# BB-M-1_0.net
KiCad netlist of a schematic drawn in EAGLE
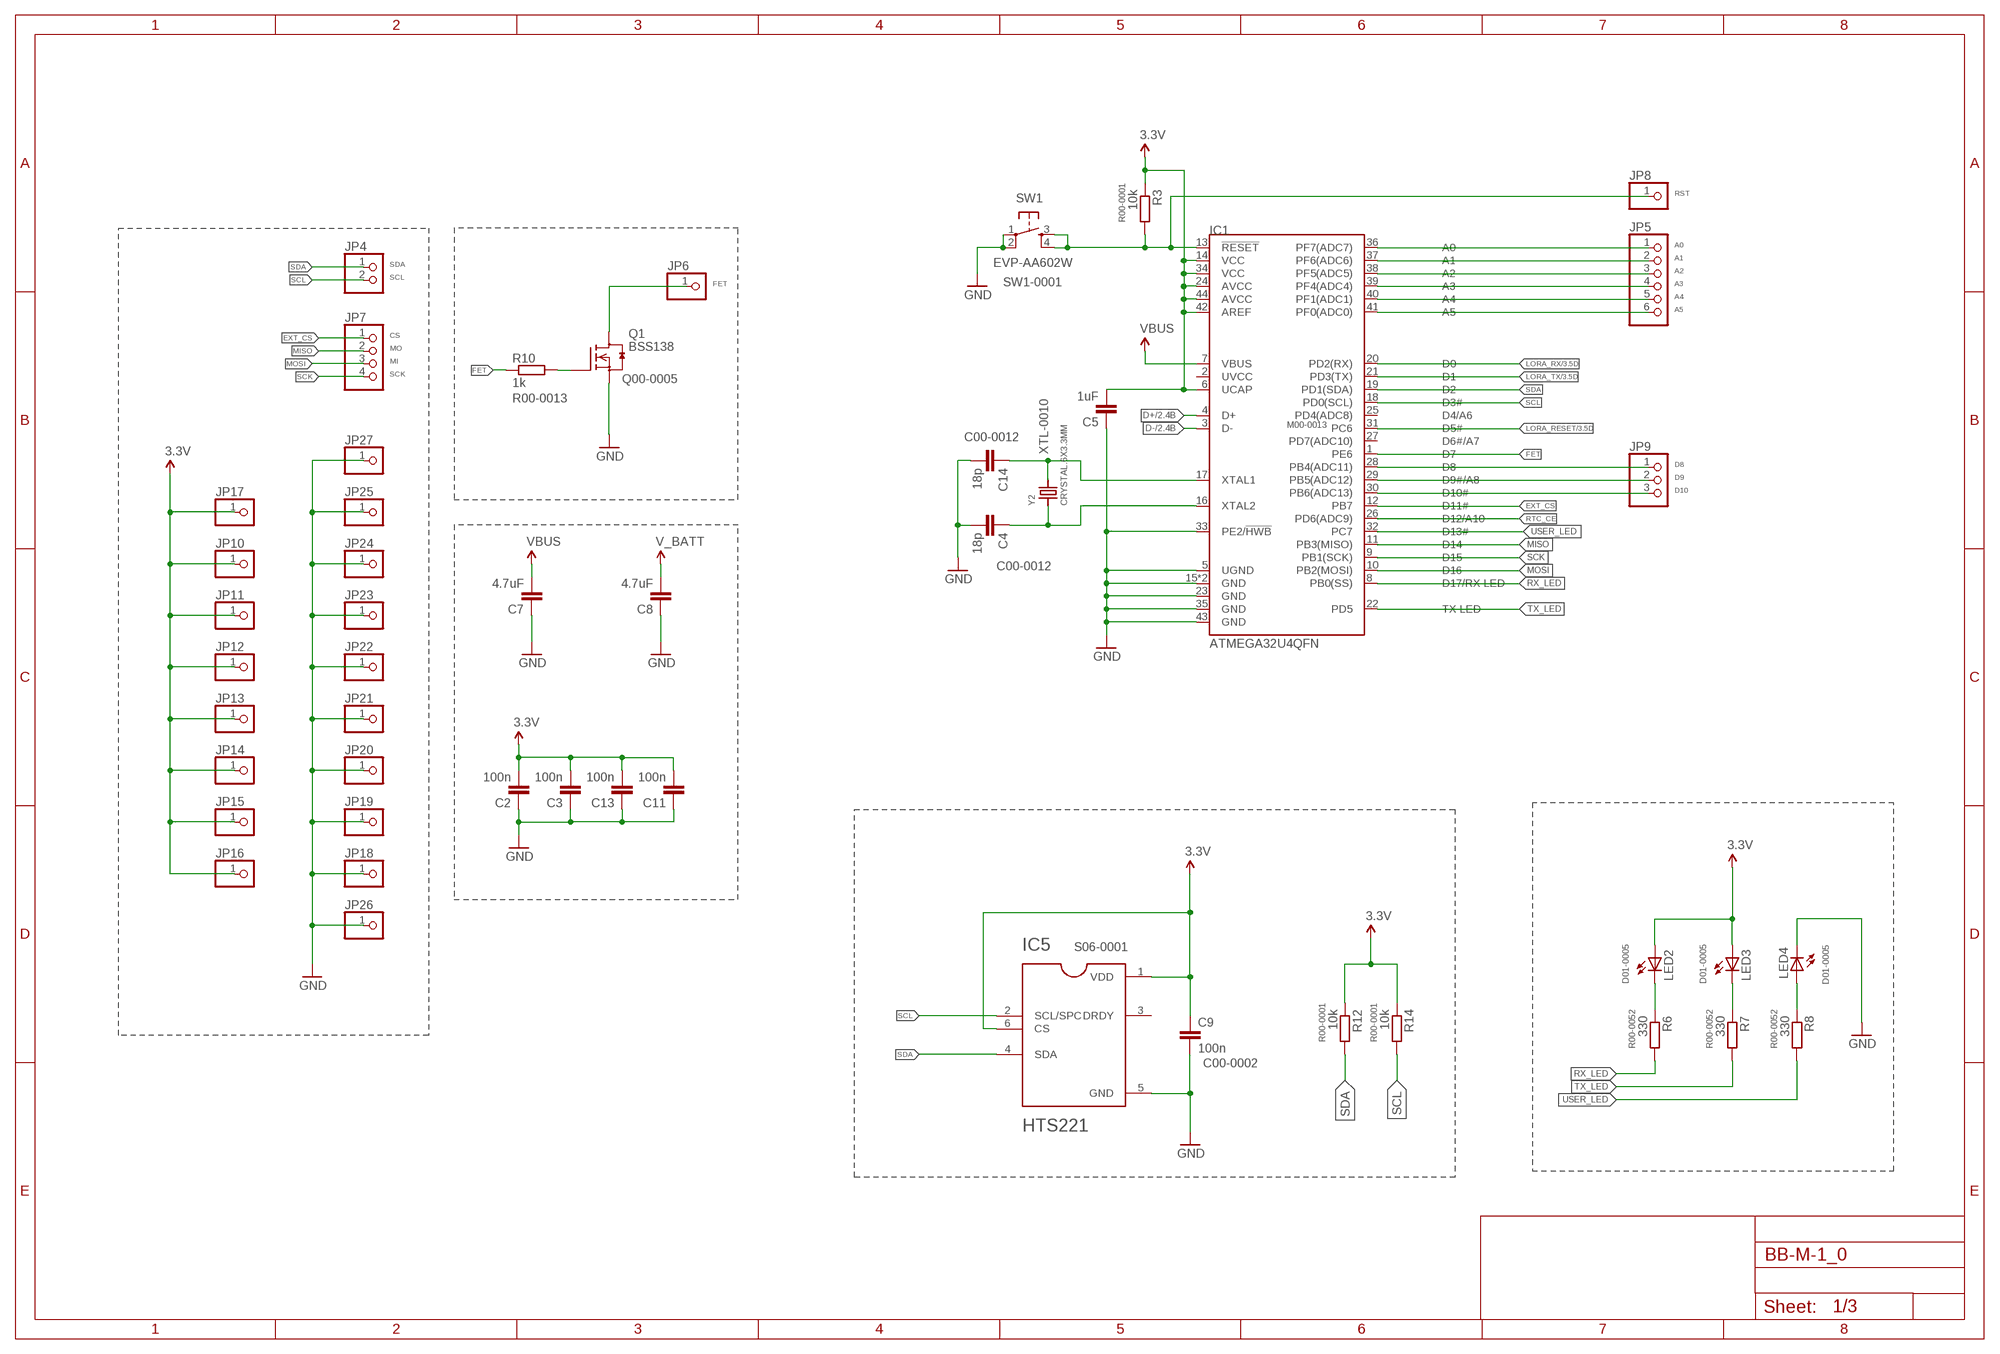
[diagram p0: schematic, sheet 1]
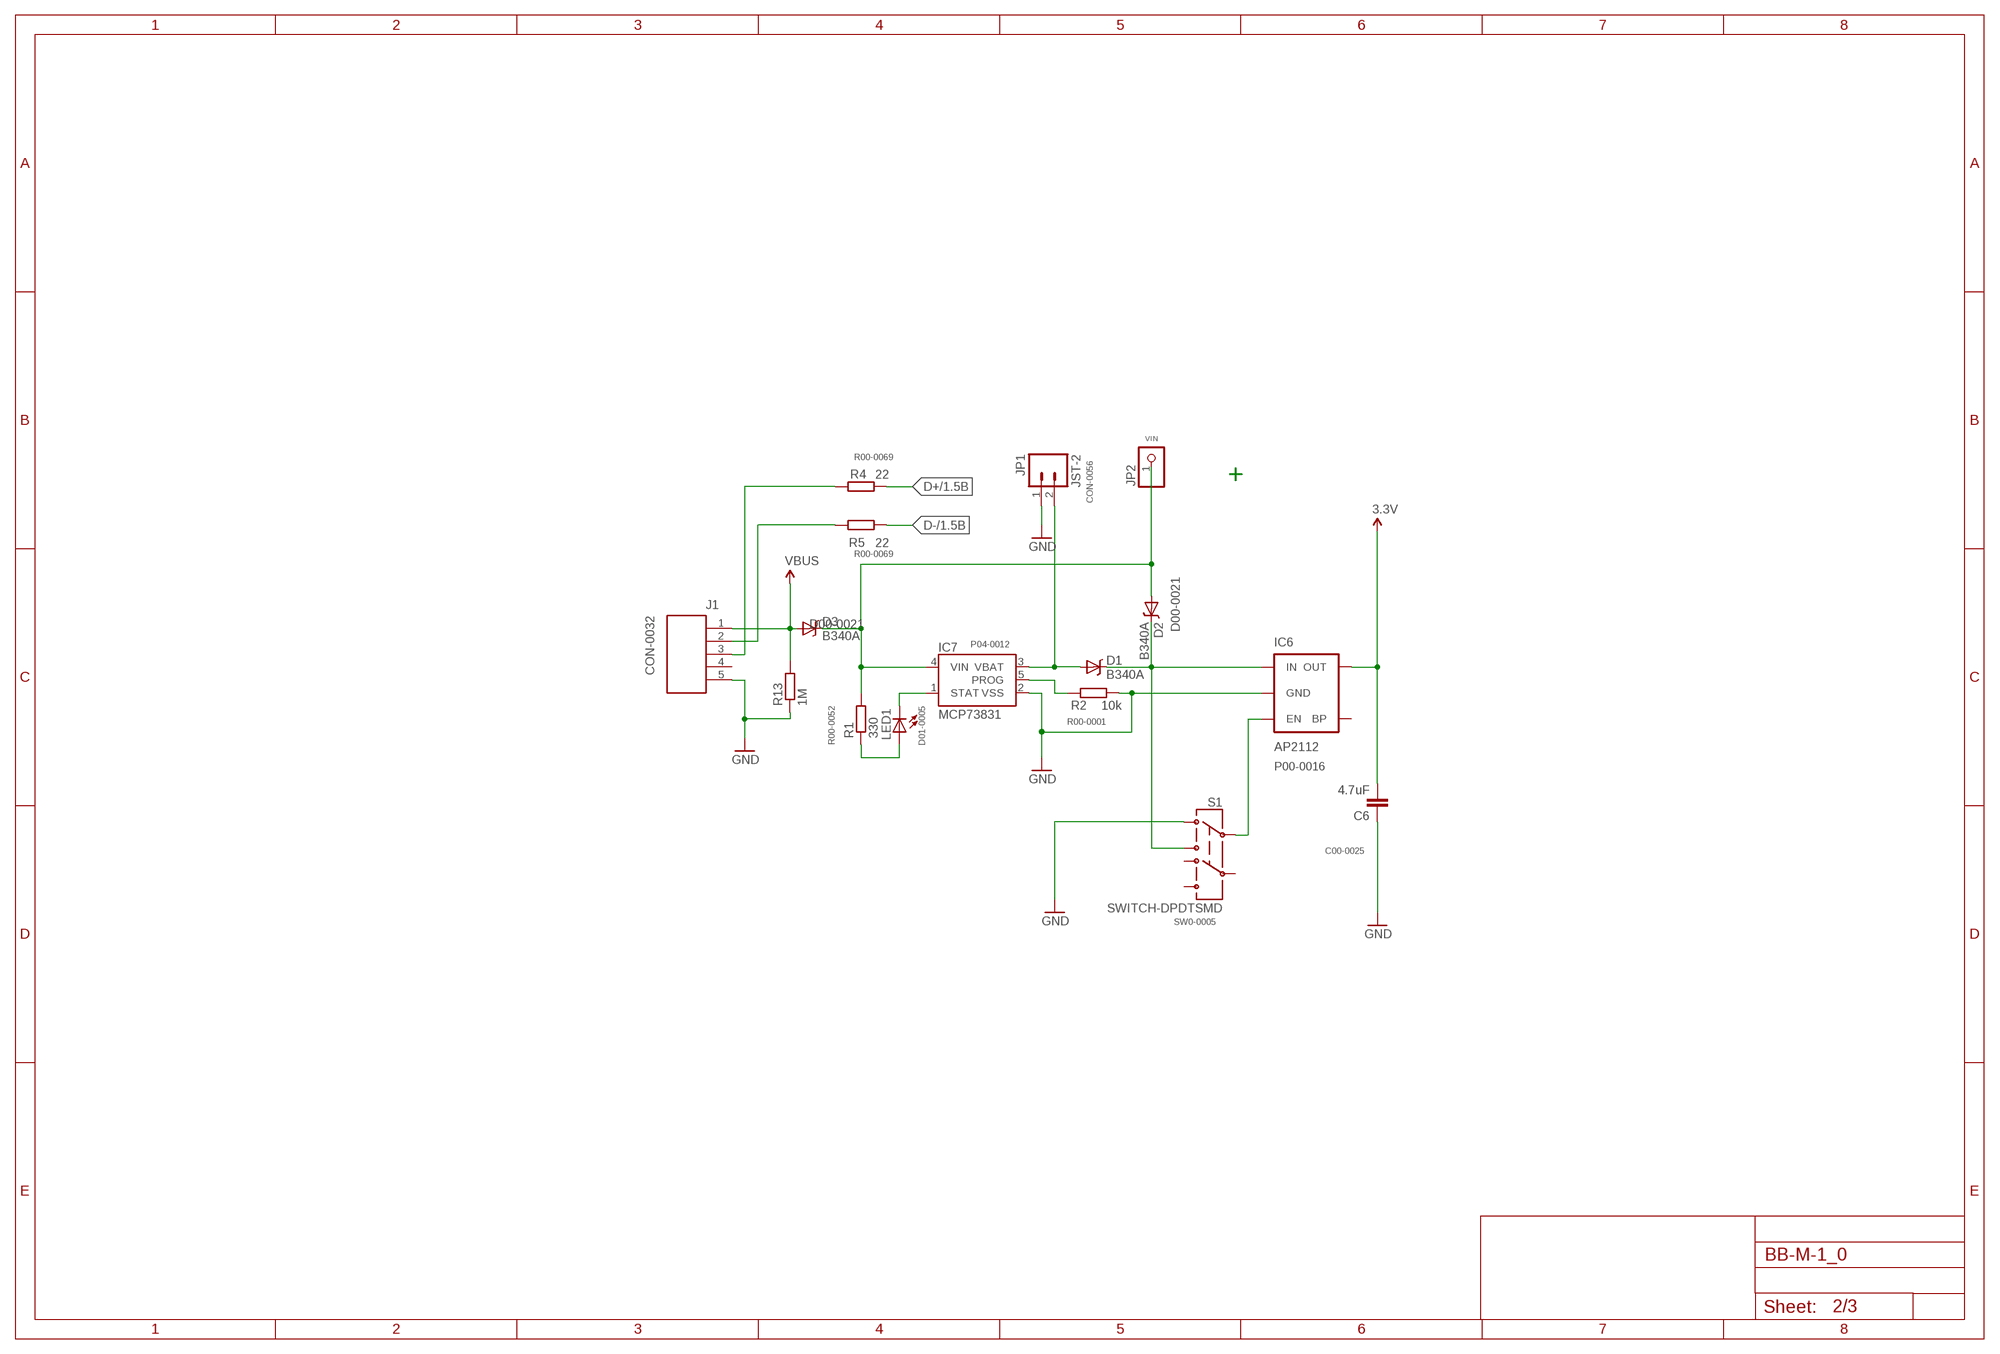
[diagram p1: schematic, sheet 2]
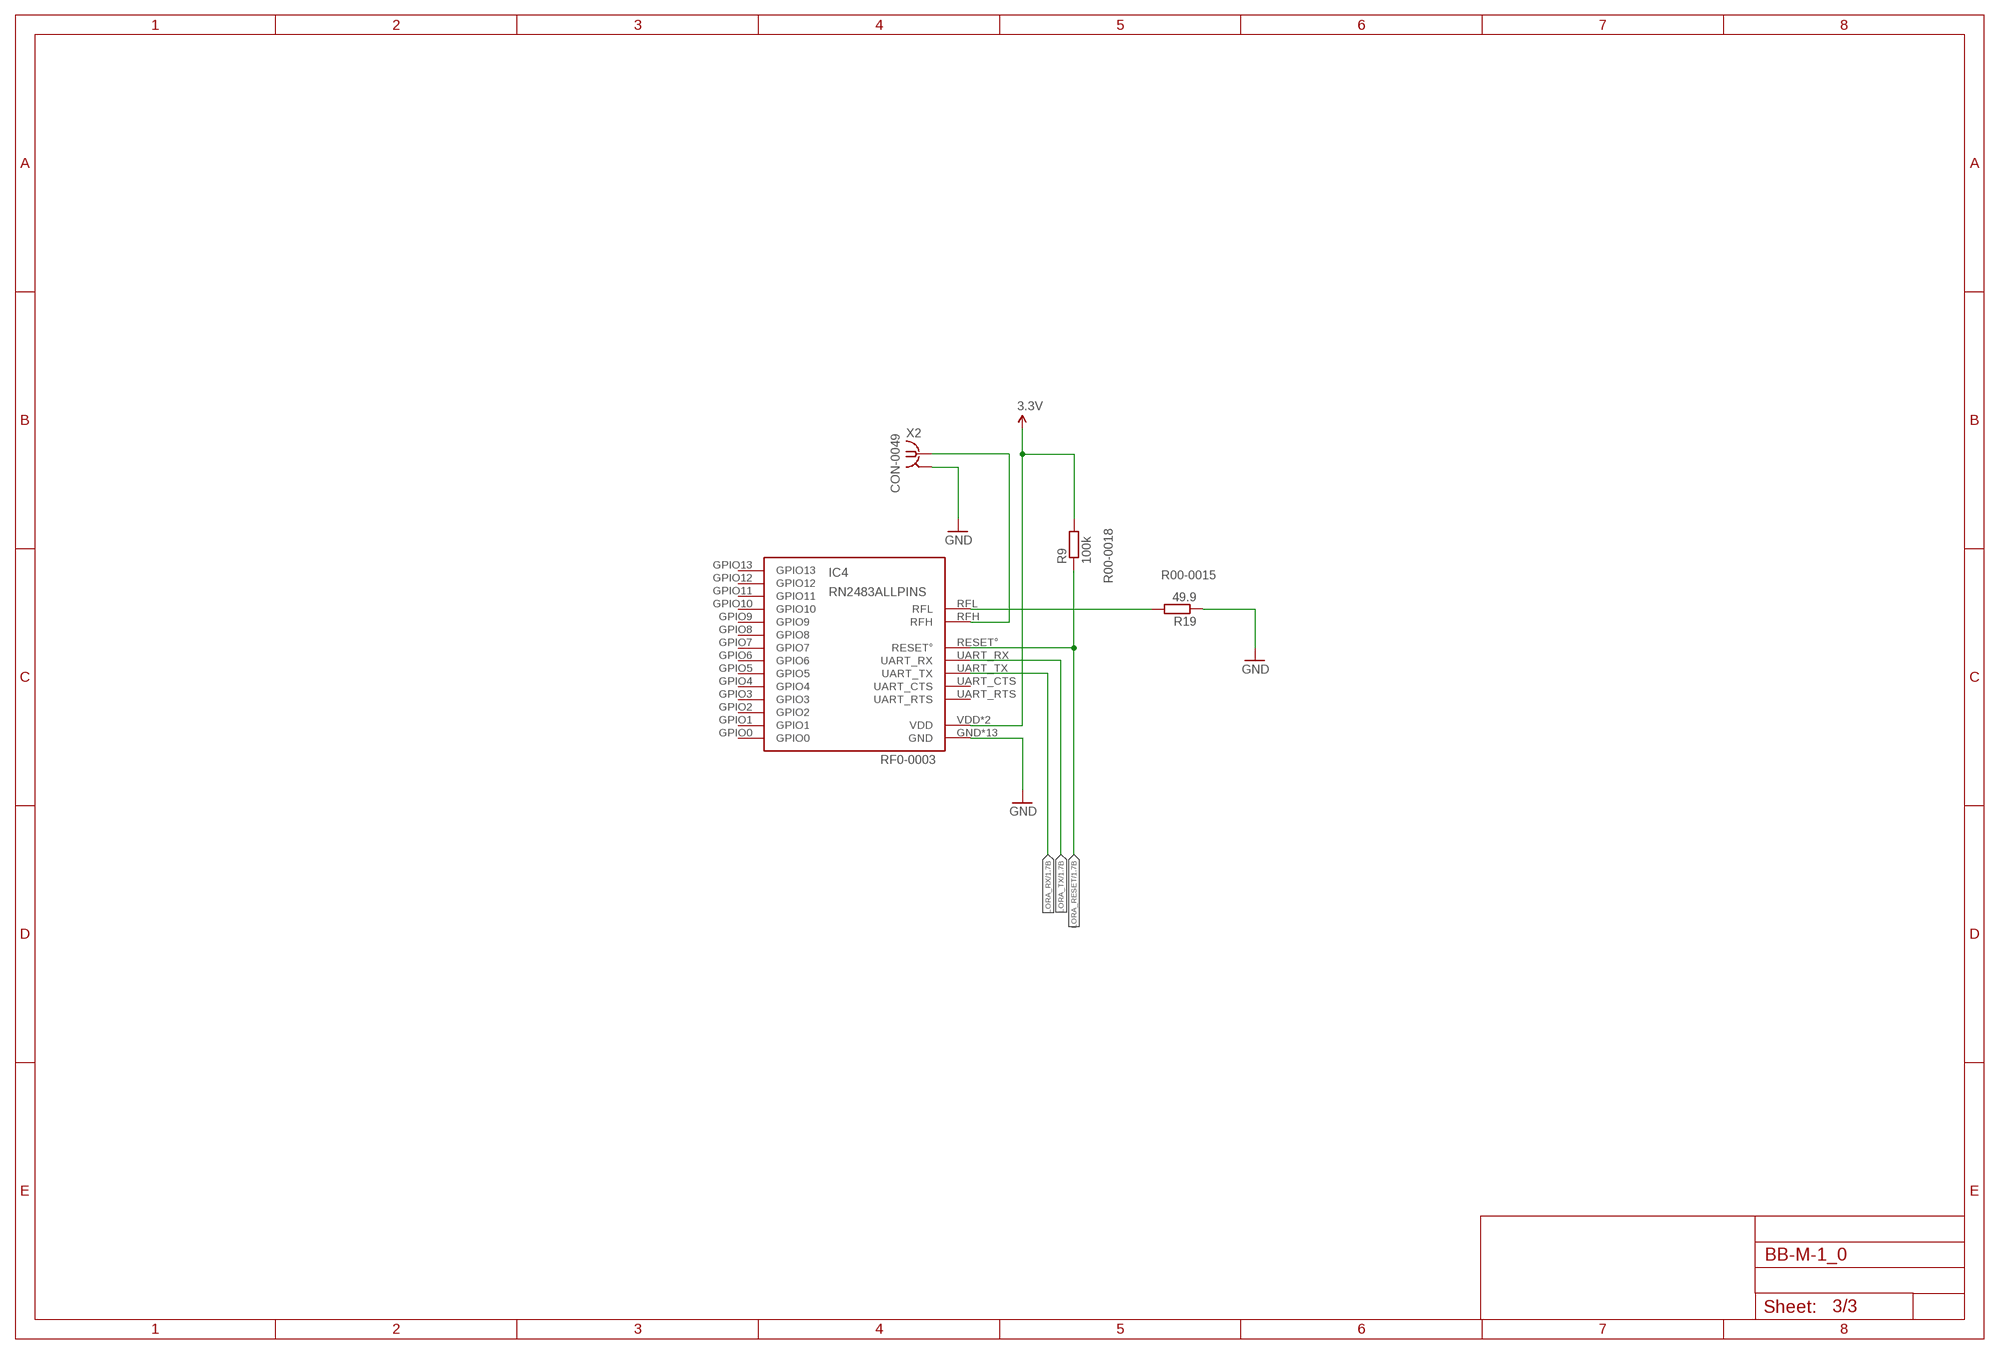
[diagram p2: schematic, sheet 3]

(export (version "E")
  (design (tool "Eeschema 10.0.6"))
  (components
    (comp (ref "IC4")
      (value "RN2483ALLPINS")
      (footprint "eagle-import:RN2483")
      (fields (field (name "NASPN") "RF0-0003"))
      (libsource (lib "eagle-import") (part "RN2483ALLPINS"))
    )
    (comp (ref "R9")
      (value "100k")
      (footprint "eagle-import:R0402")
      (fields (field (name "NASPN") "R00-0018"))
      (libsource (lib "eagle-import") (part "R-EU_R0402"))
    )
    (comp (ref "R19")
      (value "49.9")
      (footprint "eagle-import:R0402")
      (fields (field (name "NASPN") "R00-0015"))
      (libsource (lib "eagle-import") (part "R-EU_R0402"))
    )
    (comp (ref "X2")
      (value "132414")
      (footprint "eagle-import:132414")
      (fields (field (name "NASPN") "CON-0049"))
      (libsource (lib "eagle-import") (part "132414"))
    )
    (comp (ref "C2")
      (value "100n")
      (footprint "eagle-import:C0402")
      (libsource (lib "eagle-import") (part "C-EUC0402"))
    )
    (comp (ref "C3")
      (value "100n")
      (footprint "eagle-import:C0402")
      (libsource (lib "eagle-import") (part "C-EUC0402"))
    )
    (comp (ref "C4")
      (value "18p")
      (footprint "eagle-import:C0402")
      (fields (field (name "NASPN") "C00-0012"))
      (libsource (lib "eagle-import") (part "C-EUC0402"))
    )
    (comp (ref "C5")
      (value "1uF")
      (footprint "eagle-import:C0402")
      (libsource (lib "eagle-import") (part "C-EUC0402"))
    )
    (comp (ref "C7")
      (value "4.7uF")
      (footprint "eagle-import:C0603")
      (libsource (lib "eagle-import") (part "C-EUC0603"))
    )
    (comp (ref "C8")
      (value "4.7uF")
      (footprint "eagle-import:C0603")
      (libsource (lib "eagle-import") (part "C-EUC0603"))
    )
    (comp (ref "C9")
      (value "100n")
      (footprint "eagle-import:C0402")
      (fields (field (name "NASPN") "C00-0002"))
      (libsource (lib "eagle-import") (part "C-EUC0402"))
    )
    (comp (ref "C11")
      (value "100n")
      (footprint "eagle-import:C0402")
      (libsource (lib "eagle-import") (part "C-EUC0402"))
    )
    (comp (ref "C13")
      (value "100n")
      (footprint "eagle-import:C0402")
      (libsource (lib "eagle-import") (part "C-EUC0402"))
    )
    (comp (ref "C14")
      (value "18p")
      (footprint "eagle-import:C0402")
      (fields (field (name "NASPN") "C00-0012"))
      (libsource (lib "eagle-import") (part "C-EUC0402"))
    )
    (comp (ref "IC1")
      (value "ATMEGA32U4QFN")
      (footprint "eagle-import:QFN-44")
      (fields (field (name "NASPN") "M00-0013"))
      (libsource (lib "eagle-import") (part "ATMEGA32U4QFN"))
    )
    (comp (ref "IC5")
      (value "HTS221")
      (footprint "eagle-import:LGA6R75P3X2_200X200X90")
      (fields (field (name "NASPN") "S06-0001"))
      (libsource (lib "eagle-import") (part "HTS221"))
    )
    (comp (ref "JP4")
      (value "HEADER-1X2ROUND")
      (footprint "eagle-import:1X02_ROUND")
      (libsource (lib "eagle-import") (part "HEADER-1X2ROUND"))
    )
    (comp (ref "JP5")
      (value "HEADER-1X6ROUND")
      (footprint "eagle-import:1X06_ROUND")
      (libsource (lib "eagle-import") (part "HEADER-1X6ROUND"))
    )
    (comp (ref "JP6")
      (value "HEADER-1X1ROUND")
      (footprint "eagle-import:1X01_ROUND")
      (libsource (lib "eagle-import") (part "HEADER-1X1ROUND"))
    )
    (comp (ref "JP7")
      (value "HEADER-1X4ROUND")
      (footprint "eagle-import:1X04_ROUND")
      (libsource (lib "eagle-import") (part "HEADER-1X4ROUND"))
    )
    (comp (ref "JP8")
      (value "HEADER-1X1ROUND")
      (footprint "eagle-import:1X01_ROUND")
      (libsource (lib "eagle-import") (part "HEADER-1X1ROUND"))
    )
    (comp (ref "JP9")
      (value "HEADER-1X3ROUND")
      (footprint "eagle-import:1X03_ROUND")
      (libsource (lib "eagle-import") (part "HEADER-1X3ROUND"))
    )
    (comp (ref "JP10")
      (value "HEADER-1X1ROUND")
      (footprint "eagle-import:1X01_ROUND")
      (libsource (lib "eagle-import") (part "HEADER-1X1ROUND"))
    )
    (comp (ref "JP11")
      (value "HEADER-1X1ROUND")
      (footprint "eagle-import:1X01_ROUND")
      (libsource (lib "eagle-import") (part "HEADER-1X1ROUND"))
    )
    (comp (ref "JP12")
      (value "HEADER-1X1ROUND")
      (footprint "eagle-import:1X01_ROUND")
      (libsource (lib "eagle-import") (part "HEADER-1X1ROUND"))
    )
    (comp (ref "JP13")
      (value "HEADER-1X1ROUND")
      (footprint "eagle-import:1X01_ROUND")
      (libsource (lib "eagle-import") (part "HEADER-1X1ROUND"))
    )
    (comp (ref "JP14")
      (value "HEADER-1X1ROUND")
      (footprint "eagle-import:1X01_ROUND")
      (libsource (lib "eagle-import") (part "HEADER-1X1ROUND"))
    )
    (comp (ref "JP15")
      (value "HEADER-1X1ROUND")
      (footprint "eagle-import:1X01_ROUND")
      (libsource (lib "eagle-import") (part "HEADER-1X1ROUND"))
    )
    (comp (ref "JP16")
      (value "HEADER-1X1ROUND")
      (footprint "eagle-import:1X01_ROUND")
      (libsource (lib "eagle-import") (part "HEADER-1X1ROUND"))
    )
    (comp (ref "JP17")
      (value "HEADER-1X1ROUND")
      (footprint "eagle-import:1X01_ROUND")
      (libsource (lib "eagle-import") (part "HEADER-1X1ROUND"))
    )
    (comp (ref "JP18")
      (value "HEADER-1X1ROUND")
      (footprint "eagle-import:1X01_ROUND")
      (libsource (lib "eagle-import") (part "HEADER-1X1ROUND"))
    )
    (comp (ref "JP19")
      (value "HEADER-1X1ROUND")
      (footprint "eagle-import:1X01_ROUND")
      (libsource (lib "eagle-import") (part "HEADER-1X1ROUND"))
    )
    (comp (ref "JP20")
      (value "HEADER-1X1ROUND")
      (footprint "eagle-import:1X01_ROUND")
      (libsource (lib "eagle-import") (part "HEADER-1X1ROUND"))
    )
    (comp (ref "JP21")
      (value "HEADER-1X1ROUND")
      (footprint "eagle-import:1X01_ROUND")
      (libsource (lib "eagle-import") (part "HEADER-1X1ROUND"))
    )
    (comp (ref "JP22")
      (value "HEADER-1X1ROUND")
      (footprint "eagle-import:1X01_ROUND")
      (libsource (lib "eagle-import") (part "HEADER-1X1ROUND"))
    )
    (comp (ref "JP23")
      (value "HEADER-1X1ROUND")
      (footprint "eagle-import:1X01_ROUND")
      (libsource (lib "eagle-import") (part "HEADER-1X1ROUND"))
    )
    (comp (ref "JP24")
      (value "HEADER-1X1ROUND")
      (footprint "eagle-import:1X01_ROUND")
      (libsource (lib "eagle-import") (part "HEADER-1X1ROUND"))
    )
    (comp (ref "JP25")
      (value "HEADER-1X1ROUND")
      (footprint "eagle-import:1X01_ROUND")
      (libsource (lib "eagle-import") (part "HEADER-1X1ROUND"))
    )
    (comp (ref "JP26")
      (value "HEADER-1X1ROUND")
      (footprint "eagle-import:1X01_ROUND")
      (libsource (lib "eagle-import") (part "HEADER-1X1ROUND"))
    )
    (comp (ref "JP27")
      (value "HEADER-1X1ROUND")
      (footprint "eagle-import:1X01_ROUND")
      (libsource (lib "eagle-import") (part "HEADER-1X1ROUND"))
    )
    (comp (ref "LED2")
      (value "LED0603")
      (footprint "eagle-import:LED-0603")
      (fields (field (name "NASPN") "D01-0005"))
      (libsource (lib "eagle-import") (part "LED0603"))
    )
    (comp (ref "LED3")
      (value "LED0603")
      (footprint "eagle-import:LED-0603")
      (fields (field (name "NASPN") "D01-0005"))
      (libsource (lib "eagle-import") (part "LED0603"))
    )
    (comp (ref "LED4")
      (value "LED0603")
      (footprint "eagle-import:LED-0603")
      (fields (field (name "NASPN") "D01-0005"))
      (libsource (lib "eagle-import") (part "LED0603"))
    )
    (comp (ref "Q1")
      (value "BSS138")
      (footprint "eagle-import:SOT23")
      (fields (field (name "NASPN") "Q00-0005"))
      (libsource (lib "eagle-import") (part "BSS138"))
    )
    (comp (ref "R3")
      (value "10k")
      (footprint "eagle-import:R0402")
      (fields (field (name "NASPN") "R00-0001"))
      (libsource (lib "eagle-import") (part "R-EU_R0402"))
    )
    (comp (ref "R6")
      (value "330")
      (footprint "eagle-import:R0402")
      (fields (field (name "NASPN") "R00-0052"))
      (libsource (lib "eagle-import") (part "R-EU_R0402"))
    )
    (comp (ref "R7")
      (value "330")
      (footprint "eagle-import:R0402")
      (fields (field (name "NASPN") "R00-0052"))
      (libsource (lib "eagle-import") (part "R-EU_R0402"))
    )
    (comp (ref "R8")
      (value "330")
      (footprint "eagle-import:R0402")
      (fields (field (name "NASPN") "R00-0052"))
      (libsource (lib "eagle-import") (part "R-EU_R0402"))
    )
    (comp (ref "R10")
      (value "1k")
      (footprint "eagle-import:R0402")
      (fields (field (name "NASPN") "R00-0013"))
      (libsource (lib "eagle-import") (part "R-EU_R0402"))
    )
    (comp (ref "R12")
      (value "10k")
      (footprint "eagle-import:R0402")
      (fields (field (name "NASPN") "R00-0001"))
      (libsource (lib "eagle-import") (part "R-EU_R0402"))
    )
    (comp (ref "R14")
      (value "10k")
      (footprint "eagle-import:R0402")
      (fields (field (name "NASPN") "R00-0001"))
      (libsource (lib "eagle-import") (part "R-EU_R0402"))
    )
    (comp (ref "SW1")
      (value "EVP-AA602W")
      (footprint "eagle-import:UUS_BUTTON")
      (fields (field (name "NASPN") "SW1-0001"))
      (libsource (lib "eagle-import") (part "SPST_TACT"))
    )
    (comp (ref "Y2")
      (value "CRYSTAL.6X3.3MM")
      (footprint "eagle-import:6X3.3MM")
      (fields (field (name "NASPN") "XTL-0010"))
      (libsource (lib "eagle-import") (part "CRYSTAL.6X3.3MM"))
    )
    (comp (ref "C6")
      (value "4.7uF")
      (footprint "eagle-import:C0603")
      (fields (field (name "NASPN") "C00-0025"))
      (libsource (lib "eagle-import") (part "C-EUC0603"))
    )
    (comp (ref "D1")
      (value "B340A")
      (footprint "eagle-import:SMA-DIODE")
      (libsource (lib "eagle-import") (part "DIODE-SCHOTTKY_"))
    )
    (comp (ref "D2")
      (value "B340A")
      (footprint "eagle-import:SMA-DIODE")
      (fields (field (name "NASPN") "D00-0021"))
      (libsource (lib "eagle-import") (part "DIODE-SCHOTTKY_"))
    )
    (comp (ref "D3")
      (value "B340A")
      (footprint "eagle-import:SMA-DIODE")
      (fields (field (name "NASPN") "D00-0021"))
      (libsource (lib "eagle-import") (part "DIODE-SCHOTTKY_"))
    )
    (comp (ref "IC6")
      (value "AP2112")
      (footprint "eagle-import:SOT23-5")
      (fields (field (name "NASPN") "P00-0016"))
      (libsource (lib "eagle-import") (part "V_REG_MIC5219SMD"))
    )
    (comp (ref "IC7")
      (value "MCP73831")
      (footprint "eagle-import:SOT23-5")
      (fields (field (name "NASPN") "P04-0012"))
      (libsource (lib "eagle-import") (part "MCP73831"))
    )
    (comp (ref "J1")
      (value "629105136821")
      (footprint "eagle-import:629105136821")
      (fields (field (name "NASPN") "CON-0032"))
      (libsource (lib "eagle-import") (part "629105136821"))
    )
    (comp (ref "JP1")
      (value "JST-2")
      (footprint "eagle-import:JST-2-SMD")
      (fields (field (name "NASPN") "CON-0056"))
      (libsource (lib "eagle-import") (part "M02-JST-2MM-SMT"))
    )
    (comp (ref "JP2")
      (value "PINHD-1X1CB")
      (footprint "eagle-import:1X01-CLEANBIG")
      (libsource (lib "eagle-import") (part "PINHD-1X1CB"))
    )
    (comp (ref "LED1")
      (value "LED0603")
      (footprint "eagle-import:LED-0603")
      (fields (field (name "NASPN") "D01-0005"))
      (libsource (lib "eagle-import") (part "LED0603"))
    )
    (comp (ref "R1")
      (value "330")
      (footprint "eagle-import:R0402")
      (fields (field (name "NASPN") "R00-0052"))
      (libsource (lib "eagle-import") (part "R-EU_R0402"))
    )
    (comp (ref "R2")
      (value "10k")
      (footprint "eagle-import:R0402")
      (fields (field (name "NASPN") "R00-0001"))
      (libsource (lib "eagle-import") (part "R-EU_R0402"))
    )
    (comp (ref "R4")
      (value "22")
      (footprint "eagle-import:R0402")
      (fields (field (name "NASPN") "R00-0069"))
      (libsource (lib "eagle-import") (part "R-EU_R0402"))
    )
    (comp (ref "R5")
      (value "22")
      (footprint "eagle-import:R0402")
      (fields (field (name "NASPN") "R00-0069"))
      (libsource (lib "eagle-import") (part "R-EU_R0402"))
    )
    (comp (ref "R13")
      (value "1M")
      (footprint "eagle-import:R0402")
      (libsource (lib "eagle-import") (part "R-EU_R0402"))
    )
    (comp (ref "S1")
      (value "SWITCH-DPDTSMD")
      (footprint "eagle-import:AYZ0202")
      (fields (field (name "NASPN") "SW0-0005"))
      (libsource (lib "eagle-import") (part "SWITCH-DPDTSMD"))
    )
  )
  (nets
    (net (code "1") (name "3.3V") (class "Default")
      (node (ref "C11") (pin "2") (pinfunction "2_2") (pintype "passive"))
      (node (ref "C13") (pin "2") (pinfunction "2_2") (pintype "passive"))
      (node (ref "C2") (pin "2") (pinfunction "2_2") (pintype "passive"))
      (node (ref "C3") (pin "2") (pinfunction "2_2") (pintype "passive"))
      (node (ref "C5") (pin "2") (pinfunction "2_2") (pintype "passive"))
      (node (ref "C6") (pin "2") (pinfunction "2_2") (pintype "passive"))
      (node (ref "C9") (pin "1") (pinfunction "1_1") (pintype "passive"))
      (node (ref "IC1") (pin "14") (pinfunction "VCC_14") (pintype "bidirectional"))
      (node (ref "IC1") (pin "24") (pinfunction "AVCC_24") (pintype "bidirectional"))
      (node (ref "IC1") (pin "34") (pinfunction "VCC_34") (pintype "bidirectional"))
      (node (ref "IC1") (pin "42") (pinfunction "AREF_42") (pintype "bidirectional"))
      (node (ref "IC1") (pin "44") (pinfunction "AVCC_44") (pintype "bidirectional"))
      (node (ref "IC1") (pin "6") (pinfunction "UCAP_6") (pintype "bidirectional"))
      (node (ref "IC4") (pin "VDD") (pinfunction "VDD_VDD") (pintype "bidirectional"))
      (node (ref "IC4") (pin "VDD2") (pinfunction "VDD_VDD2") (pintype "bidirectional"))
      (node (ref "IC5") (pin "1") (pinfunction "VDD_1") (pintype "power_in"))
      (node (ref "IC5") (pin "6") (pinfunction "CS_6") (pintype "input"))
      (node (ref "IC6") (pin "5") (pinfunction "OUT_5") (pintype "passive"))
      (node (ref "JP10") (pin "1") (pinfunction "1_1") (pintype "passive"))
      (node (ref "JP11") (pin "1") (pinfunction "1_1") (pintype "passive"))
      (node (ref "JP12") (pin "1") (pinfunction "1_1") (pintype "passive"))
      (node (ref "JP13") (pin "1") (pinfunction "1_1") (pintype "passive"))
      (node (ref "JP14") (pin "1") (pinfunction "1_1") (pintype "passive"))
      (node (ref "JP15") (pin "1") (pinfunction "1_1") (pintype "passive"))
      (node (ref "JP16") (pin "1") (pinfunction "1_1") (pintype "passive"))
      (node (ref "JP17") (pin "1") (pinfunction "1_1") (pintype "passive"))
      (node (ref "LED2") (pin "A") (pinfunction "A_A") (pintype "passive"))
      (node (ref "LED3") (pin "A") (pinfunction "A_A") (pintype "passive"))
      (node (ref "R12") (pin "1") (pinfunction "1_1") (pintype "passive"))
      (node (ref "R14") (pin "1") (pinfunction "1_1") (pintype "passive"))
      (node (ref "R3") (pin "1") (pinfunction "1_1") (pintype "passive"))
      (node (ref "R9") (pin "2") (pinfunction "2_2") (pintype "passive"))
    )
    (net (code "2") (name "5V") (class "Default")
      (node (ref "C7") (pin "2") (pinfunction "2_2") (pintype "passive"))
      (node (ref "D3") (pin "A") (pinfunction "A_A") (pintype "passive"))
      (node (ref "IC1") (pin "7") (pinfunction "VBUS_7") (pintype "bidirectional"))
      (node (ref "J1") (pin "1") (pinfunction "1_1") (pintype "passive"))
      (node (ref "R13") (pin "2") (pinfunction "2_2") (pintype "passive"))
    )
    (net (code "3") (name "D+") (class "Default")
      (node (ref "IC1") (pin "4") (pinfunction "D+_4") (pintype "bidirectional"))
      (node (ref "R4") (pin "1") (pinfunction "1_1") (pintype "passive"))
    )
    (net (code "4") (name "D-") (class "Default")
      (node (ref "IC1") (pin "3") (pinfunction "D-_3") (pintype "bidirectional"))
      (node (ref "R5") (pin "1") (pinfunction "1_1") (pintype "passive"))
    )
    (net (code "5") (name "EXT_CS") (class "Default")
      (node (ref "IC1") (pin "12") (pinfunction "PB7_12") (pintype "bidirectional"))
      (node (ref "JP7") (pin "1") (pinfunction "1_1") (pintype "passive"))
    )
    (net (code "6") (name "FET") (class "Default")
      (node (ref "IC1") (pin "1") (pinfunction "PE6_1") (pintype "bidirectional"))
      (node (ref "R10") (pin "1") (pinfunction "1_1") (pintype "passive"))
    )
    (net (code "7") (name "GND") (class "Default")
      (node (ref "C11") (pin "1") (pinfunction "1_1") (pintype "passive"))
      (node (ref "C13") (pin "1") (pinfunction "1_1") (pintype "passive"))
      (node (ref "C14") (pin "2") (pinfunction "2_2") (pintype "passive"))
      (node (ref "C2") (pin "1") (pinfunction "1_1") (pintype "passive"))
      (node (ref "C3") (pin "1") (pinfunction "1_1") (pintype "passive"))
      (node (ref "C4") (pin "2") (pinfunction "2_2") (pintype "passive"))
      (node (ref "C5") (pin "1") (pinfunction "1_1") (pintype "passive"))
      (node (ref "C6") (pin "1") (pinfunction "1_1") (pintype "passive"))
      (node (ref "C7") (pin "1") (pinfunction "1_1") (pintype "passive"))
      (node (ref "C8") (pin "1") (pinfunction "1_1") (pintype "passive"))
      (node (ref "C9") (pin "2") (pinfunction "2_2") (pintype "passive"))
      (node (ref "IC1") (pin "15") (pinfunction "GND_15") (pintype "bidirectional"))
      (node (ref "IC1") (pin "23") (pinfunction "GND_23") (pintype "bidirectional"))
      (node (ref "IC1") (pin "33") (pinfunction "PE2/~{HWB}_33") (pintype "bidirectional"))
      (node (ref "IC1") (pin "35") (pinfunction "GND_35") (pintype "bidirectional"))
      (node (ref "IC1") (pin "43") (pinfunction "GND_43") (pintype "bidirectional"))
      (node (ref "IC1") (pin "5") (pinfunction "UGND_5") (pintype "bidirectional"))
      (node (ref "IC1") (pin "EPAD") (pinfunction "GND_EPAD") (pintype "bidirectional"))
      (node (ref "IC4") (pin "GND") (pinfunction "GND_GND") (pintype "bidirectional"))
      (node (ref "IC4") (pin "GND1") (pinfunction "GND_GND1") (pintype "bidirectional"))
      (node (ref "IC4") (pin "GND10") (pinfunction "GND_GND10") (pintype "bidirectional"))
      (node (ref "IC4") (pin "GND11") (pinfunction "GND_GND11") (pintype "bidirectional"))
      (node (ref "IC4") (pin "GND12") (pinfunction "GND_GND12") (pintype "bidirectional"))
      (node (ref "IC4") (pin "GND2") (pinfunction "GND_GND2") (pintype "bidirectional"))
      (node (ref "IC4") (pin "GND3") (pinfunction "GND_GND3") (pintype "bidirectional"))
      (node (ref "IC4") (pin "GND4") (pinfunction "GND_GND4") (pintype "bidirectional"))
      (node (ref "IC4") (pin "GND5") (pinfunction "GND_GND5") (pintype "bidirectional"))
      (node (ref "IC4") (pin "GND6") (pinfunction "GND_GND6") (pintype "bidirectional"))
      (node (ref "IC4") (pin "GND7") (pinfunction "GND_GND7") (pintype "bidirectional"))
      (node (ref "IC4") (pin "GND8") (pinfunction "GND_GND8") (pintype "bidirectional"))
      (node (ref "IC4") (pin "GND9") (pinfunction "GND_GND9") (pintype "bidirectional"))
      (node (ref "IC5") (pin "5") (pinfunction "GND_5") (pintype "passive"))
      (node (ref "IC6") (pin "2") (pinfunction "GND_2") (pintype "input"))
      (node (ref "IC7") (pin "2") (pinfunction "VSS_2") (pintype "power_in"))
      (node (ref "J1") (pin "5") (pinfunction "5_5") (pintype "passive"))
      (node (ref "JP1") (pin "1") (pinfunction "2_1") (pintype "passive"))
      (node (ref "JP18") (pin "1") (pinfunction "1_1") (pintype "passive"))
      (node (ref "JP19") (pin "1") (pinfunction "1_1") (pintype "passive"))
      (node (ref "JP20") (pin "1") (pinfunction "1_1") (pintype "passive"))
      (node (ref "JP21") (pin "1") (pinfunction "1_1") (pintype "passive"))
      (node (ref "JP22") (pin "1") (pinfunction "1_1") (pintype "passive"))
      (node (ref "JP23") (pin "1") (pinfunction "1_1") (pintype "passive"))
      (node (ref "JP24") (pin "1") (pinfunction "1_1") (pintype "passive"))
      (node (ref "JP25") (pin "1") (pinfunction "1_1") (pintype "passive"))
      (node (ref "JP26") (pin "1") (pinfunction "1_1") (pintype "passive"))
      (node (ref "JP27") (pin "1") (pinfunction "1_1") (pintype "passive"))
      (node (ref "LED4") (pin "C") (pinfunction "C_C") (pintype "passive"))
      (node (ref "Q1") (pin "2") (pinfunction "S_2") (pintype "passive"))
      (node (ref "R13") (pin "1") (pinfunction "1_1") (pintype "passive"))
      (node (ref "R19") (pin "1") (pinfunction "1_1") (pintype "passive"))
      (node (ref "R2") (pin "1") (pinfunction "1_1") (pintype "passive"))
      (node (ref "S1") (pin "1") (pinfunction "1_1") (pintype "bidirectional"))
      (node (ref "SW1") (pin "1") (pinfunction "P_1") (pintype "passive"))
      (node (ref "SW1") (pin "2") (pinfunction "P1_2") (pintype "passive"))
      (node (ref "X2") (pin "G@1") (pinfunction "GND_G@1") (pintype "passive"))
      (node (ref "X2") (pin "G@2") (pinfunction "GND_G@2") (pintype "passive"))
      (node (ref "X2") (pin "G@3") (pinfunction "GND_G@3") (pintype "passive"))
      (node (ref "X2") (pin "G@4") (pinfunction "GND_G@4") (pintype "passive"))
    )
    (net (code "8") (name "LORA_RESET") (class "Default")
      (node (ref "IC1") (pin "31") (pinfunction "PC6_31") (pintype "bidirectional"))
      (node (ref "IC4") (pin "RESET°") (pinfunction "RESET°_RESET°") (pintype "bidirectional"))
      (node (ref "R9") (pin "1") (pinfunction "1_1") (pintype "passive"))
    )
    (net (code "9") (name "LORA_RX") (class "Default")
      (node (ref "IC1") (pin "20") (pinfunction "PD2(RX)_20") (pintype "bidirectional"))
      (node (ref "IC4") (pin "UART_TX") (pinfunction "UART_TX_UART_TX") (pintype "bidirectional"))
    )
    (net (code "10") (name "LORA_TX") (class "Default")
      (node (ref "IC1") (pin "21") (pinfunction "PD3(TX)_21") (pintype "bidirectional"))
      (node (ref "IC4") (pin "UART_RX") (pinfunction "UART_RX_UART_RX") (pintype "bidirectional"))
    )
    (net (code "11") (name "MISO") (class "Default")
      (node (ref "IC1") (pin "11") (pinfunction "PB3(MISO)_11") (pintype "bidirectional"))
      (node (ref "JP7") (pin "2") (pinfunction "2_2") (pintype "passive"))
    )
    (net (code "12") (name "MOSI") (class "Default")
      (node (ref "IC1") (pin "10") (pinfunction "PB2(MOSI)_10") (pintype "bidirectional"))
      (node (ref "JP7") (pin "3") (pinfunction "3_3") (pintype "passive"))
    )
    (net (code "13") (name "Net-(IC1-PB4(ADC11))") (class "Default")
      (node (ref "IC1") (pin "28") (pinfunction "PB4(ADC11)_28") (pintype "bidirectional"))
      (node (ref "JP9") (pin "1") (pinfunction "1_1") (pintype "passive"))
    )
    (net (code "14") (name "Net-(IC1-PB5(ADC12))") (class "Default")
      (node (ref "IC1") (pin "29") (pinfunction "PB5(ADC12)_29") (pintype "bidirectional"))
      (node (ref "JP9") (pin "2") (pinfunction "2_2") (pintype "passive"))
    )
    (net (code "15") (name "Net-(IC1-PB6(ADC13))") (class "Default")
      (node (ref "IC1") (pin "30") (pinfunction "PB6(ADC13)_30") (pintype "bidirectional"))
      (node (ref "JP9") (pin "3") (pinfunction "3_3") (pintype "passive"))
    )
    (net (code "16") (name "Net-(IC1-PF0(ADC0))") (class "Default")
      (node (ref "IC1") (pin "41") (pinfunction "PF0(ADC0)_41") (pintype "bidirectional"))
      (node (ref "JP5") (pin "6") (pinfunction "6_6") (pintype "passive"))
    )
    (net (code "17") (name "Net-(IC1-PF1(ADC1))") (class "Default")
      (node (ref "IC1") (pin "40") (pinfunction "PF1(ADC1)_40") (pintype "bidirectional"))
      (node (ref "JP5") (pin "5") (pinfunction "5_5") (pintype "passive"))
    )
    (net (code "18") (name "Net-(IC1-PF4(ADC4))") (class "Default")
      (node (ref "IC1") (pin "39") (pinfunction "PF4(ADC4)_39") (pintype "bidirectional"))
      (node (ref "JP5") (pin "4") (pinfunction "4_4") (pintype "passive"))
    )
    (net (code "19") (name "Net-(IC1-PF5(ADC5))") (class "Default")
      (node (ref "IC1") (pin "38") (pinfunction "PF5(ADC5)_38") (pintype "bidirectional"))
      (node (ref "JP5") (pin "3") (pinfunction "3_3") (pintype "passive"))
    )
    (net (code "20") (name "Net-(IC1-PF6(ADC6))") (class "Default")
      (node (ref "IC1") (pin "37") (pinfunction "PF6(ADC6)_37") (pintype "bidirectional"))
      (node (ref "JP5") (pin "2") (pinfunction "2_2") (pintype "passive"))
    )
    (net (code "21") (name "Net-(IC1-PF7(ADC7))") (class "Default")
      (node (ref "IC1") (pin "36") (pinfunction "PF7(ADC7)_36") (pintype "bidirectional"))
      (node (ref "JP5") (pin "1") (pinfunction "1_1") (pintype "passive"))
    )
    (net (code "22") (name "Net-(IC1-XTAL1)") (class "Default")
      (node (ref "C14") (pin "1") (pinfunction "1_1") (pintype "passive"))
      (node (ref "IC1") (pin "17") (pinfunction "XTAL1_17") (pintype "bidirectional"))
      (node (ref "Y2") (pin "2") (pinfunction "2_2") (pintype "passive"))
    )
    (net (code "23") (name "Net-(IC1-XTAL2)") (class "Default")
      (node (ref "C4") (pin "1") (pinfunction "1_1") (pintype "passive"))
      (node (ref "IC1") (pin "16") (pinfunction "XTAL2_16") (pintype "bidirectional"))
      (node (ref "Y2") (pin "1") (pinfunction "1_1") (pintype "passive"))
    )
    (net (code "24") (name "Net-(IC1-~{RESET})") (class "Default")
      (node (ref "IC1") (pin "13") (pinfunction "~{RESET}_13") (pintype "bidirectional"))
      (node (ref "JP8") (pin "1") (pinfunction "1_1") (pintype "passive"))
      (node (ref "R3") (pin "2") (pinfunction "2_2") (pintype "passive"))
      (node (ref "SW1") (pin "3") (pinfunction "S_3") (pintype "passive"))
      (node (ref "SW1") (pin "4") (pinfunction "S1_4") (pintype "passive"))
    )
    (net (code "25") (name "Net-(IC4-PadRFH)") (class "Default")
      (node (ref "IC4") (pin "RFH") (pinfunction "RFH_RFH") (pintype "bidirectional"))
      (node (ref "X2") (pin "1") (pinfunction "1_1") (pintype "passive"))
    )
    (net (code "26") (name "Net-(IC4-PadRFL)") (class "Default")
      (node (ref "IC4") (pin "RFL") (pinfunction "RFL_RFL") (pintype "bidirectional"))
      (node (ref "R19") (pin "2") (pinfunction "2_2") (pintype "passive"))
    )
    (net (code "27") (name "Net-(IC6-EN)") (class "Default")
      (node (ref "IC6") (pin "3") (pinfunction "EN_3") (pintype "input"))
      (node (ref "S1") (pin "2") (pinfunction "2_2") (pintype "bidirectional"))
    )
    (net (code "28") (name "Net-(IC6-IN)") (class "Default")
      (node (ref "D1") (pin "C") (pinfunction "C_C") (pintype "passive"))
      (node (ref "D2") (pin "C") (pinfunction "C_C") (pintype "passive"))
      (node (ref "IC6") (pin "1") (pinfunction "IN_1") (pintype "input"))
      (node (ref "S1") (pin "3") (pinfunction "3_3") (pintype "bidirectional"))
    )
    (net (code "29") (name "Net-(IC7-PROG)") (class "Default")
      (node (ref "IC7") (pin "5") (pinfunction "PROG_5") (pintype "input"))
      (node (ref "R2") (pin "2") (pinfunction "2_2") (pintype "passive"))
    )
    (net (code "30") (name "Net-(IC7-STAT)") (class "Default")
      (node (ref "IC7") (pin "1") (pinfunction "STAT_1") (pintype "output"))
      (node (ref "LED1") (pin "C") (pinfunction "C_C") (pintype "passive"))
    )
    (net (code "31") (name "Net-(IC7-VIN)") (class "Default")
      (node (ref "D2") (pin "A") (pinfunction "A_A") (pintype "passive"))
      (node (ref "D3") (pin "C") (pinfunction "C_C") (pintype "passive"))
      (node (ref "IC7") (pin "4") (pinfunction "VIN_4") (pintype "power_in"))
      (node (ref "JP2") (pin "1") (pinfunction "1_1") (pintype "passive"))
      (node (ref "R1") (pin "2") (pinfunction "2_2") (pintype "passive"))
    )
    (net (code "32") (name "Net-(J1-Pad2)") (class "Default")
      (node (ref "J1") (pin "2") (pinfunction "2_2") (pintype "passive"))
      (node (ref "R5") (pin "2") (pinfunction "2_2") (pintype "passive"))
    )
    (net (code "33") (name "Net-(J1-Pad3)") (class "Default")
      (node (ref "J1") (pin "3") (pinfunction "3_3") (pintype "passive"))
      (node (ref "R4") (pin "2") (pinfunction "2_2") (pintype "passive"))
    )
    (net (code "34") (name "Net-(LED1-PadA)") (class "Default")
      (node (ref "LED1") (pin "A") (pinfunction "A_A") (pintype "passive"))
      (node (ref "R1") (pin "1") (pinfunction "1_1") (pintype "passive"))
    )
    (net (code "35") (name "Net-(LED2-PadC)") (class "Default")
      (node (ref "LED2") (pin "C") (pinfunction "C_C") (pintype "passive"))
      (node (ref "R6") (pin "1") (pinfunction "1_1") (pintype "passive"))
    )
    (net (code "36") (name "Net-(LED3-PadC)") (class "Default")
      (node (ref "LED3") (pin "C") (pinfunction "C_C") (pintype "passive"))
      (node (ref "R7") (pin "1") (pinfunction "1_1") (pintype "passive"))
    )
    (net (code "37") (name "Net-(LED4-PadA)") (class "Default")
      (node (ref "LED4") (pin "A") (pinfunction "A_A") (pintype "passive"))
      (node (ref "R8") (pin "1") (pinfunction "1_1") (pintype "passive"))
    )
    (net (code "38") (name "Net-(Q1-D)") (class "Default")
      (node (ref "JP6") (pin "1") (pinfunction "1_1") (pintype "passive"))
      (node (ref "Q1") (pin "3") (pinfunction "D_3") (pintype "passive"))
    )
    (net (code "39") (name "Net-(Q1-G)") (class "Default")
      (node (ref "Q1") (pin "1") (pinfunction "G_1") (pintype "passive"))
      (node (ref "R10") (pin "2") (pinfunction "2_2") (pintype "passive"))
    )
    (net (code "40") (name "RTC_CE") (class "Default")
      (node (ref "IC1") (pin "26") (pinfunction "PD6(ADC9)_26") (pintype "bidirectional"))
    )
    (net (code "41") (name "RX_LED") (class "Default")
      (node (ref "IC1") (pin "8") (pinfunction "PB0(SS)_8") (pintype "bidirectional"))
      (node (ref "R6") (pin "2") (pinfunction "2_2") (pintype "passive"))
    )
    (net (code "42") (name "SCK") (class "Default")
      (node (ref "IC1") (pin "9") (pinfunction "PB1(SCK)_9") (pintype "bidirectional"))
      (node (ref "JP7") (pin "4") (pinfunction "4_4") (pintype "passive"))
    )
    (net (code "43") (name "SCL") (class "Default")
      (node (ref "IC1") (pin "18") (pinfunction "PD0(SCL)_18") (pintype "bidirectional"))
      (node (ref "IC5") (pin "2") (pinfunction "SCL/SPC_2") (pintype "input"))
      (node (ref "JP4") (pin "2") (pinfunction "2_2") (pintype "passive"))
      (node (ref "R14") (pin "2") (pinfunction "2_2") (pintype "passive"))
    )
    (net (code "44") (name "SDA") (class "Default")
      (node (ref "IC1") (pin "19") (pinfunction "PD1(SDA)_19") (pintype "bidirectional"))
      (node (ref "IC5") (pin "4") (pinfunction "SDA_4") (pintype "bidirectional"))
      (node (ref "JP4") (pin "1") (pinfunction "1_1") (pintype "passive"))
      (node (ref "R12") (pin "2") (pinfunction "2_2") (pintype "passive"))
    )
    (net (code "45") (name "TX_LED") (class "Default")
      (node (ref "IC1") (pin "22") (pinfunction "PD5_22") (pintype "bidirectional"))
      (node (ref "R7") (pin "2") (pinfunction "2_2") (pintype "passive"))
    )
    (net (code "46") (name "USER_LED") (class "Default")
      (node (ref "IC1") (pin "32") (pinfunction "PC7_32") (pintype "bidirectional"))
      (node (ref "R8") (pin "2") (pinfunction "2_2") (pintype "passive"))
    )
    (net (code "47") (name "V_BATT") (class "Default")
      (node (ref "C8") (pin "2") (pinfunction "2_2") (pintype "passive"))
      (node (ref "D1") (pin "A") (pinfunction "A_A") (pintype "passive"))
      (node (ref "IC7") (pin "3") (pinfunction "VBAT_3") (pintype "power_in"))
      (node (ref "JP1") (pin "2") (pinfunction "1_2") (pintype "passive"))
    )
    (net (code "48") (name "unconnected-(IC1-PD4(ADC8)-Pad25)") (class "Default")
      (node (ref "IC1") (pin "25") (pinfunction "PD4(ADC8)_25") (pintype "bidirectional"))
    )
    (net (code "49") (name "unconnected-(IC1-PD7(ADC10)-Pad27)") (class "Default")
      (node (ref "IC1") (pin "27") (pinfunction "PD7(ADC10)_27") (pintype "bidirectional"))
    )
    (net (code "50") (name "unconnected-(IC1-UVCC-Pad2)") (class "Default")
      (node (ref "IC1") (pin "2") (pinfunction "UVCC_2") (pintype "bidirectional"))
    )
    (net (code "51") (name "unconnected-(IC4-PadGPIO0)") (class "Default")
      (node (ref "IC4") (pin "GPIO0") (pinfunction "GPIO0_GPIO0") (pintype "bidirectional"))
    )
    (net (code "52") (name "unconnected-(IC4-PadGPIO1)") (class "Default")
      (node (ref "IC4") (pin "GPIO1") (pinfunction "GPIO1_GPIO1") (pintype "bidirectional"))
    )
    (net (code "53") (name "unconnected-(IC4-PadGPIO2)") (class "Default")
      (node (ref "IC4") (pin "GPIO2") (pinfunction "GPIO2_GPIO2") (pintype "bidirectional"))
    )
    (net (code "54") (name "unconnected-(IC4-PadGPIO3)") (class "Default")
      (node (ref "IC4") (pin "GPIO3") (pinfunction "GPIO3_GPIO3") (pintype "bidirectional"))
    )
    (net (code "55") (name "unconnected-(IC4-PadGPIO4)") (class "Default")
      (node (ref "IC4") (pin "GPIO4") (pinfunction "GPIO4_GPIO4") (pintype "bidirectional"))
    )
    (net (code "56") (name "unconnected-(IC4-PadGPIO5)") (class "Default")
      (node (ref "IC4") (pin "GPIO5") (pinfunction "GPIO5_GPIO5") (pintype "bidirectional"))
    )
    (net (code "57") (name "unconnected-(IC4-PadGPIO6)") (class "Default")
      (node (ref "IC4") (pin "GPIO6") (pinfunction "GPIO6_GPIO6") (pintype "bidirectional"))
    )
    (net (code "58") (name "unconnected-(IC4-PadGPIO7)") (class "Default")
      (node (ref "IC4") (pin "GPIO7") (pinfunction "GPIO7_GPIO7") (pintype "bidirectional"))
    )
    (net (code "59") (name "unconnected-(IC4-PadGPIO8)") (class "Default")
      (node (ref "IC4") (pin "GPIO8") (pinfunction "GPIO8_GPIO8") (pintype "bidirectional"))
    )
    (net (code "60") (name "unconnected-(IC4-PadGPIO9)") (class "Default")
      (node (ref "IC4") (pin "GPIO9") (pinfunction "GPIO9_GPIO9") (pintype "bidirectional"))
    )
    (net (code "61") (name "unconnected-(IC4-PadGPIO10)") (class "Default")
      (node (ref "IC4") (pin "GPIO10") (pinfunction "GPIO10_GPIO10") (pintype "bidirectional"))
    )
    (net (code "62") (name "unconnected-(IC4-PadGPIO11)") (class "Default")
      (node (ref "IC4") (pin "GPIO11") (pinfunction "GPIO11_GPIO11") (pintype "bidirectional"))
    )
    (net (code "63") (name "unconnected-(IC4-PadGPIO12)") (class "Default")
      (node (ref "IC4") (pin "GPIO12") (pinfunction "GPIO12_GPIO12") (pintype "bidirectional"))
    )
    (net (code "64") (name "unconnected-(IC4-PadGPIO13)") (class "Default")
      (node (ref "IC4") (pin "GPIO13") (pinfunction "GPIO13_GPIO13") (pintype "bidirectional"))
    )
    (net (code "65") (name "unconnected-(IC4-PadUART_CTS)") (class "Default")
      (node (ref "IC4") (pin "UART_CTS") (pinfunction "UART_CTS_UART_CTS") (pintype "bidirectional"))
    )
    (net (code "66") (name "unconnected-(IC4-PadUART_RTS)") (class "Default")
      (node (ref "IC4") (pin "UART_RTS") (pinfunction "UART_RTS_UART_RTS") (pintype "bidirectional"))
    )
    (net (code "67") (name "unconnected-(IC5-DRDY-Pad3)") (class "Default")
      (node (ref "IC5") (pin "3") (pinfunction "DRDY_3") (pintype "output"))
    )
    (net (code "68") (name "unconnected-(IC6-BP-Pad4)") (class "Default")
      (node (ref "IC6") (pin "4") (pinfunction "BP_4") (pintype "input"))
    )
    (net (code "69") (name "unconnected-(J1-Pad4)") (class "Default")
      (node (ref "J1") (pin "4") (pinfunction "4_4") (pintype "passive"))
    )
    (net (code "70") (name "unconnected-(S1-Pad4)") (class "Default")
      (node (ref "S1") (pin "4") (pinfunction "4_4") (pintype "bidirectional"))
    )
    (net (code "71") (name "unconnected-(S1-Pad5)") (class "Default")
      (node (ref "S1") (pin "5") (pinfunction "5_5") (pintype "bidirectional"))
    )
    (net (code "72") (name "unconnected-(S1-Pad6)") (class "Default")
      (node (ref "S1") (pin "6") (pinfunction "6_6") (pintype "bidirectional"))
    )
  )
)
